# motorEncoder.net
KiCad netlist of a schematic drawn in Altium Designer
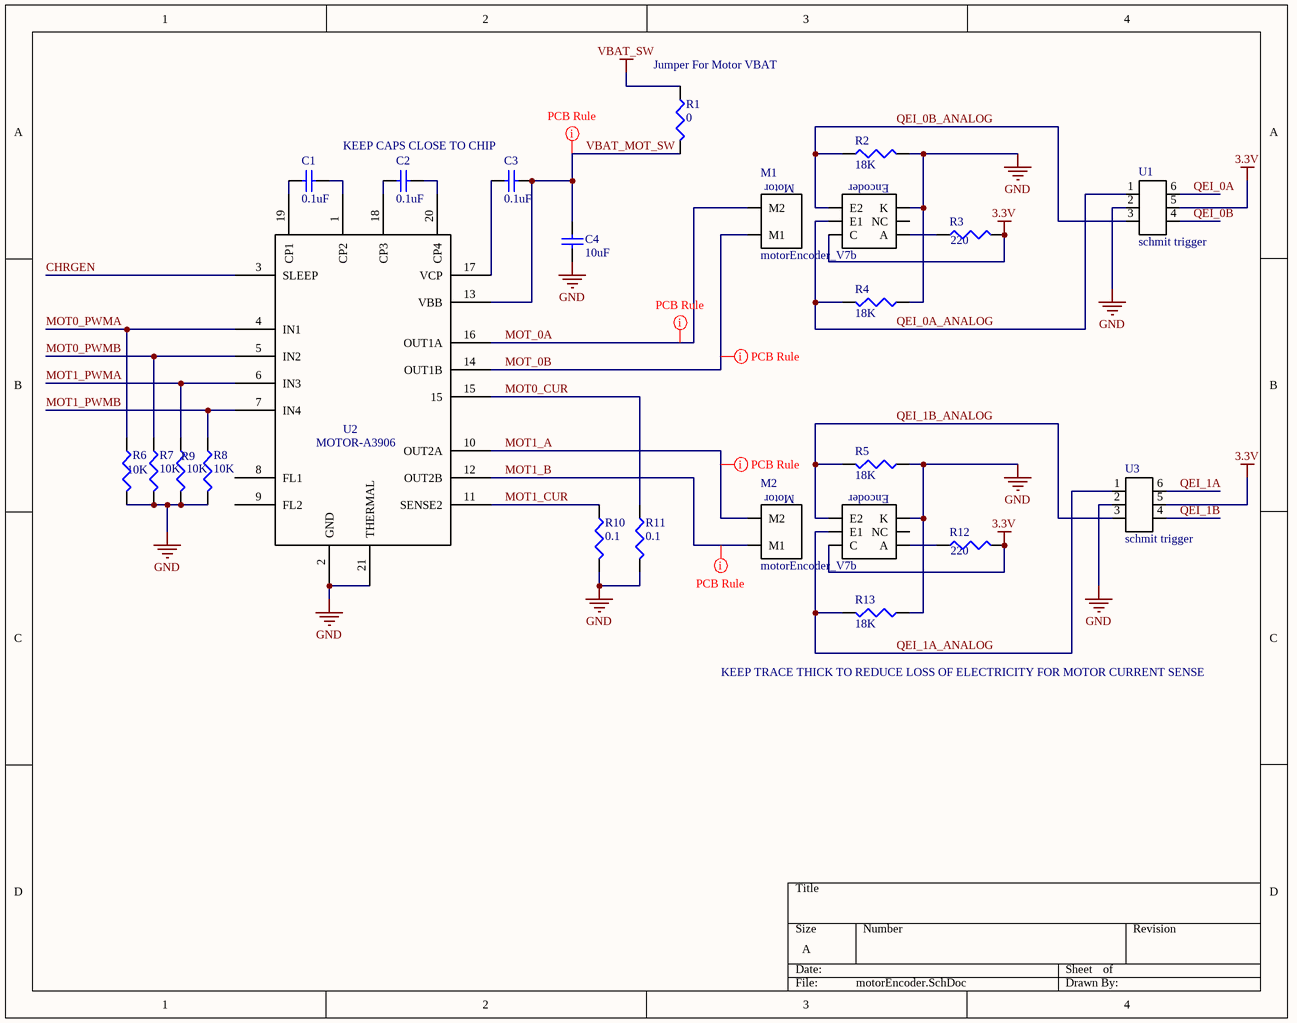
[diagram p0: motorEncoder.SchDoc]

(export (version "E")
  (design (tool "Eeschema 10.0.6"))
  (components
    (comp (ref "C1")
      (value "0.1uF")
      (footprint "CAPC1005L")
      (description "Capacitor (Semiconductor SIM Model)")
      (fields (field (name "Comment") "Cap Semi") (field (name "PUBLISHER") "Altium Limited"))
      (libsource (lib "Miscellaneous Devices") (part "Cap Semi"))
    )
    (comp (ref "C2")
      (value "0.1uF")
      (footprint "CAPC1005L")
      (description "Capacitor (Semiconductor SIM Model)")
      (fields (field (name "Comment") "Cap Semi") (field (name "PUBLISHER") "Altium Limited"))
      (libsource (lib "Miscellaneous Devices") (part "Cap Semi"))
    )
    (comp (ref "C3")
      (value "0.1uF")
      (footprint "CAPC1005L")
      (description "Capacitor (Semiconductor SIM Model)")
      (fields (field (name "Comment") "Cap Semi") (field (name "PUBLISHER") "Altium Limited"))
      (libsource (lib "Miscellaneous Devices") (part "Cap Semi"))
    )
    (comp (ref "C4")
      (value "10uF")
      (footprint "CAPC1608L")
      (description "Capacitor (Semiconductor SIM Model)")
      (fields (field (name "Comment") "Cap Semi") (field (name "PUBLISHER") "Altium Limited"))
      (libsource (lib "Miscellaneous Devices") (part "Cap Semi"))
    )
    (comp (ref "M1")
      (value "motorEncoder_V7b")
      (footprint "motorEncoder_V7b")
      (libsource (lib "mrone") (part "motorEncoder_V7b"))
    )
    (comp (ref "M2")
      (value "motorEncoder_V7b")
      (footprint "motorEncoder_V7b")
      (libsource (lib "mrone") (part "motorEncoder_V7b"))
    )
    (comp (ref "R1")
      (value "0")
      (footprint "RESC3225L")
      (description "Resistor")
      (fields (field (name "Comment") "Res3") (field (name "PUBLISHER") "Altium Limited"))
      (libsource (lib "Miscellaneous Devices") (part "Res3"))
    )
    (comp (ref "R2")
      (value "18K")
      (footprint "RESC1608L")
      (description "Resistor")
      (fields (field (name "PUBLISHER") "Altium Limited"))
      (libsource (lib "Miscellaneous Devices") (part "Res3"))
    )
    (comp (ref "R3")
      (value "220")
      (footprint "RESC1608L")
      (description "Resistor")
      (fields (field (name "PUBLISHER") "Altium Limited"))
      (libsource (lib "Miscellaneous Devices") (part "Res3"))
    )
    (comp (ref "R4")
      (value "18K")
      (footprint "RESC1608L")
      (description "Resistor")
      (fields (field (name "PUBLISHER") "Altium Limited"))
      (libsource (lib "Miscellaneous Devices") (part "Res3"))
    )
    (comp (ref "R5")
      (value "18K")
      (footprint "RESC1608L")
      (description "Resistor")
      (fields (field (name "PUBLISHER") "Altium Limited"))
      (libsource (lib "Miscellaneous Devices") (part "Res3"))
    )
    (comp (ref "R6")
      (value "10K")
      (footprint "RESC1608L")
      (description "Resistor")
      (fields (field (name "Comment") "Res3") (field (name "PUBLISHER") "Altium Limited"))
      (libsource (lib "Miscellaneous Devices") (part "Res3"))
    )
    (comp (ref "R7")
      (value "10K")
      (footprint "RESC1608L")
      (description "Resistor")
      (fields (field (name "Comment") "Res3") (field (name "PUBLISHER") "Altium Limited"))
      (libsource (lib "Miscellaneous Devices") (part "Res3"))
    )
    (comp (ref "R8")
      (value "10K")
      (footprint "RESC1608L")
      (description "Resistor")
      (fields (field (name "Comment") "Res3") (field (name "PUBLISHER") "Altium Limited"))
      (libsource (lib "Miscellaneous Devices") (part "Res3"))
    )
    (comp (ref "R9")
      (value "10K")
      (footprint "RESC1608L")
      (description "Resistor")
      (fields (field (name "Comment") "Res3") (field (name "PUBLISHER") "Altium Limited"))
      (libsource (lib "Miscellaneous Devices") (part "Res3"))
    )
    (comp (ref "R10")
      (value "0.1")
      (footprint "RESC1608L")
      (description "Resistor")
      (fields (field (name "Comment") "Res3") (field (name "PUBLISHER") "Altium Limited"))
      (libsource (lib "Miscellaneous Devices") (part "Res3"))
    )
    (comp (ref "R11")
      (value "0.1")
      (footprint "RESC1608L")
      (description "Resistor")
      (fields (field (name "Comment") "Res3") (field (name "PUBLISHER") "Altium Limited"))
      (libsource (lib "Miscellaneous Devices") (part "Res3"))
    )
    (comp (ref "R12")
      (value "220")
      (footprint "RESC1608L")
      (description "Resistor")
      (fields (field (name "PUBLISHER") "Altium Limited"))
      (libsource (lib "Miscellaneous Devices") (part "Res3"))
    )
    (comp (ref "R13")
      (value "18K")
      (footprint "RESC1608L")
      (description "Resistor")
      (fields (field (name "PUBLISHER") "Altium Limited"))
      (libsource (lib "Miscellaneous Devices") (part "Res3"))
    )
    (comp (ref "U1")
      (value "schmit trigger")
      (footprint "DCK(R-PDSO-C6)")
      (libsource (lib "mrone") (part "schmit trigger"))
    )
    (comp (ref "U2")
      (value "MOTOR-A3906")
      (footprint "QFN-20")
      (libsource (lib "V2_altium") (part "MOTOR-A3906"))
    )
    (comp (ref "U3")
      (value "schmit trigger")
      (footprint "DCK(R-PDSO-C6)")
      (libsource (lib "mrone") (part "schmit trigger"))
    )
  )
  (nets
    (net (code "2") (name "/CHRGEN") (class "Default")
      (node (ref "U2") (pin "3") (pinfunction "SLEEP_3") (pintype "passive"))
    )
    (net (code "3") (name "/MOT0_CUR") (class "Default")
      (node (ref "R11") (pin "1") (pinfunction "1_1") (pintype "passive"))
      (node (ref "U2") (pin "15") (pinfunction "15_15") (pintype "passive"))
    )
    (net (code "4") (name "/MOT0_PWMA") (class "Default")
      (node (ref "R6") (pin "1") (pinfunction "1_1") (pintype "passive"))
      (node (ref "U2") (pin "4") (pinfunction "IN1_4") (pintype "passive"))
    )
    (net (code "5") (name "/MOT0_PWMB") (class "Default")
      (node (ref "R7") (pin "1") (pinfunction "1_1") (pintype "passive"))
      (node (ref "U2") (pin "5") (pinfunction "IN2_5") (pintype "passive"))
    )
    (net (code "6") (name "/MOT1_A") (class "Default")
      (node (ref "M2") (pin "M2") (pinfunction "M2_M2") (pintype "passive"))
      (node (ref "U2") (pin "10") (pinfunction "OUT2A_10") (pintype "passive"))
    )
    (net (code "7") (name "/MOT1_B") (class "Default")
      (node (ref "M2") (pin "M1") (pinfunction "M1_M1") (pintype "passive"))
      (node (ref "U2") (pin "12") (pinfunction "OUT2B_12") (pintype "passive"))
    )
    (net (code "8") (name "/MOT1_CUR") (class "Default")
      (node (ref "R10") (pin "1") (pinfunction "1_1") (pintype "passive"))
      (node (ref "U2") (pin "11") (pinfunction "SENSE2_11") (pintype "passive"))
    )
    (net (code "9") (name "/MOT1_PWMA") (class "Default")
      (node (ref "R9") (pin "1") (pinfunction "1_1") (pintype "passive"))
      (node (ref "U2") (pin "6") (pinfunction "IN3_6") (pintype "passive"))
    )
    (net (code "10") (name "/MOT1_PWMB") (class "Default")
      (node (ref "R8") (pin "1") (pinfunction "1_1") (pintype "passive"))
      (node (ref "U2") (pin "7") (pinfunction "IN4_7") (pintype "passive"))
    )
    (net (code "11") (name "/MOT_0A") (class "Default")
      (node (ref "M1") (pin "M2") (pinfunction "M2_M2") (pintype "passive"))
      (node (ref "U2") (pin "16") (pinfunction "OUT1A_16") (pintype "passive"))
    )
    (net (code "12") (name "/MOT_0B") (class "Default")
      (node (ref "M1") (pin "M1") (pinfunction "M1_M1") (pintype "passive"))
      (node (ref "U2") (pin "14") (pinfunction "OUT1B_14") (pintype "passive"))
    )
    (net (code "13") (name "/QEI_0A") (class "Default")
      (node (ref "U1") (pin "6") (pinfunction "4_6") (pintype "passive"))
    )
    (net (code "14") (name "/QEI_0A_ANALOG") (class "Default")
      (node (ref "M1") (pin "E1") (pinfunction "E1_E1") (pintype "passive"))
      (node (ref "R4") (pin "2") (pinfunction "2_2") (pintype "passive"))
      (node (ref "U1") (pin "1") (pinfunction "1_1") (pintype "passive"))
    )
    (net (code "15") (name "/QEI_0B") (class "Default")
      (node (ref "U1") (pin "4") (pinfunction "4_4") (pintype "passive"))
    )
    (net (code "16") (name "/QEI_0B_ANALOG") (class "Default")
      (node (ref "M1") (pin "E2") (pinfunction "E2_E2") (pintype "passive"))
      (node (ref "R2") (pin "1") (pinfunction "1_1") (pintype "passive"))
      (node (ref "U1") (pin "3") (pinfunction "3_3") (pintype "passive"))
    )
    (net (code "17") (name "/QEI_1A") (class "Default")
      (node (ref "U3") (pin "6") (pinfunction "4_6") (pintype "passive"))
    )
    (net (code "18") (name "/QEI_1A_ANALOG") (class "Default")
      (node (ref "M2") (pin "E1") (pinfunction "E1_E1") (pintype "passive"))
      (node (ref "R13") (pin "2") (pinfunction "2_2") (pintype "passive"))
      (node (ref "U3") (pin "1") (pinfunction "1_1") (pintype "passive"))
    )
    (net (code "19") (name "/QEI_1B") (class "Default")
      (node (ref "U3") (pin "4") (pinfunction "4_4") (pintype "passive"))
    )
    (net (code "20") (name "/QEI_1B_ANALOG") (class "Default")
      (node (ref "M2") (pin "E2") (pinfunction "E2_E2") (pintype "passive"))
      (node (ref "R5") (pin "2") (pinfunction "2_2") (pintype "passive"))
      (node (ref "U3") (pin "3") (pinfunction "3_3") (pintype "passive"))
    )
    (net (code "21") (name "/VBAT_MOT_SW") (class "Default")
      (node (ref "C3") (pin "1") (pinfunction "1_1") (pintype "passive"))
      (node (ref "C4") (pin "2") (pinfunction "2_2") (pintype "passive"))
      (node (ref "R1") (pin "2") (pinfunction "2_2") (pintype "passive"))
      (node (ref "U2") (pin "13") (pinfunction "VBB_13") (pintype "passive"))
    )
    (net (code "22") (name "3.3V") (class "Default")
      (node (ref "M1") (pin "C") (pinfunction "C_C") (pintype "passive"))
      (node (ref "M2") (pin "C") (pinfunction "C_C") (pintype "passive"))
      (node (ref "R12") (pin "2") (pinfunction "2_2") (pintype "passive"))
      (node (ref "R3") (pin "2") (pinfunction "2_2") (pintype "passive"))
      (node (ref "U1") (pin "5") (pinfunction "5_5") (pintype "passive"))
      (node (ref "U3") (pin "5") (pinfunction "5_5") (pintype "passive"))
    )
    (net (code "23") (name "GND") (class "Default")
      (node (ref "C4") (pin "1") (pinfunction "1_1") (pintype "passive"))
      (node (ref "M1") (pin "K") (pinfunction "K_K") (pintype "passive"))
      (node (ref "M2") (pin "K") (pinfunction "K_K") (pintype "passive"))
      (node (ref "R10") (pin "2") (pinfunction "2_2") (pintype "passive"))
      (node (ref "R11") (pin "2") (pinfunction "2_2") (pintype "passive"))
      (node (ref "R13") (pin "1") (pinfunction "1_1") (pintype "passive"))
      (node (ref "R2") (pin "2") (pinfunction "2_2") (pintype "passive"))
      (node (ref "R4") (pin "1") (pinfunction "1_1") (pintype "passive"))
      (node (ref "R5") (pin "1") (pinfunction "1_1") (pintype "passive"))
      (node (ref "R6") (pin "2") (pinfunction "2_2") (pintype "passive"))
      (node (ref "R7") (pin "2") (pinfunction "2_2") (pintype "passive"))
      (node (ref "R8") (pin "2") (pinfunction "2_2") (pintype "passive"))
      (node (ref "R9") (pin "2") (pinfunction "2_2") (pintype "passive"))
      (node (ref "U1") (pin "2") (pinfunction "2_2") (pintype "passive"))
      (node (ref "U2") (pin "2") (pinfunction "GND_2") (pintype "passive"))
      (node (ref "U2") (pin "21") (pinfunction "THERMAL_21") (pintype "passive"))
      (node (ref "U3") (pin "2") (pinfunction "2_2") (pintype "passive"))
    )
    (net (code "24") (name "Net-(M1-PadA)") (class "Default")
      (node (ref "M1") (pin "A") (pinfunction "A_A") (pintype "passive"))
      (node (ref "R3") (pin "1") (pinfunction "1_1") (pintype "passive"))
    )
    (net (code "25") (name "Net-(M2-PadA)") (class "Default")
      (node (ref "M2") (pin "A") (pinfunction "A_A") (pintype "passive"))
      (node (ref "R12") (pin "1") (pinfunction "1_1") (pintype "passive"))
    )
    (net (code "26") (name "Net-(U2-CP1)") (class "Default")
      (node (ref "C1") (pin "1") (pinfunction "1_1") (pintype "passive"))
      (node (ref "U2") (pin "19") (pinfunction "CP1_19") (pintype "passive"))
    )
    (net (code "27") (name "Net-(U2-CP2)") (class "Default")
      (node (ref "C1") (pin "2") (pinfunction "2_2") (pintype "passive"))
      (node (ref "U2") (pin "1") (pinfunction "CP2_1") (pintype "passive"))
    )
    (net (code "28") (name "Net-(U2-CP3)") (class "Default")
      (node (ref "C2") (pin "1") (pinfunction "1_1") (pintype "passive"))
      (node (ref "U2") (pin "18") (pinfunction "CP3_18") (pintype "passive"))
    )
    (net (code "29") (name "Net-(U2-CP4)") (class "Default")
      (node (ref "C2") (pin "2") (pinfunction "2_2") (pintype "passive"))
      (node (ref "U2") (pin "20") (pinfunction "CP4_20") (pintype "passive"))
    )
    (net (code "30") (name "Net-(U2-VCP)") (class "Default")
      (node (ref "C3") (pin "2") (pinfunction "2_2") (pintype "passive"))
      (node (ref "U2") (pin "17") (pinfunction "VCP_17") (pintype "passive"))
    )
    (net (code "31") (name "VBAT_SW") (class "Default")
      (node (ref "R1") (pin "1") (pinfunction "1_1") (pintype "passive"))
    )
    (net (code "32") (name "unconnected-(M1-PadNC)") (class "Default")
      (node (ref "M1") (pin "NC") (pinfunction "NC_NC") (pintype "passive"))
    )
    (net (code "33") (name "unconnected-(M2-PadNC)") (class "Default")
      (node (ref "M2") (pin "NC") (pinfunction "NC_NC") (pintype "passive"))
    )
    (net (code "34") (name "unconnected-(U2-FL1-Pad8)") (class "Default")
      (node (ref "U2") (pin "8") (pinfunction "FL1_8") (pintype "passive"))
    )
    (net (code "35") (name "unconnected-(U2-FL2-Pad9)") (class "Default")
      (node (ref "U2") (pin "9") (pinfunction "FL2_9") (pintype "passive"))
    )
  )
)
